# Main_v0_2.net
KiCad netlist of a schematic drawn in EAGLE
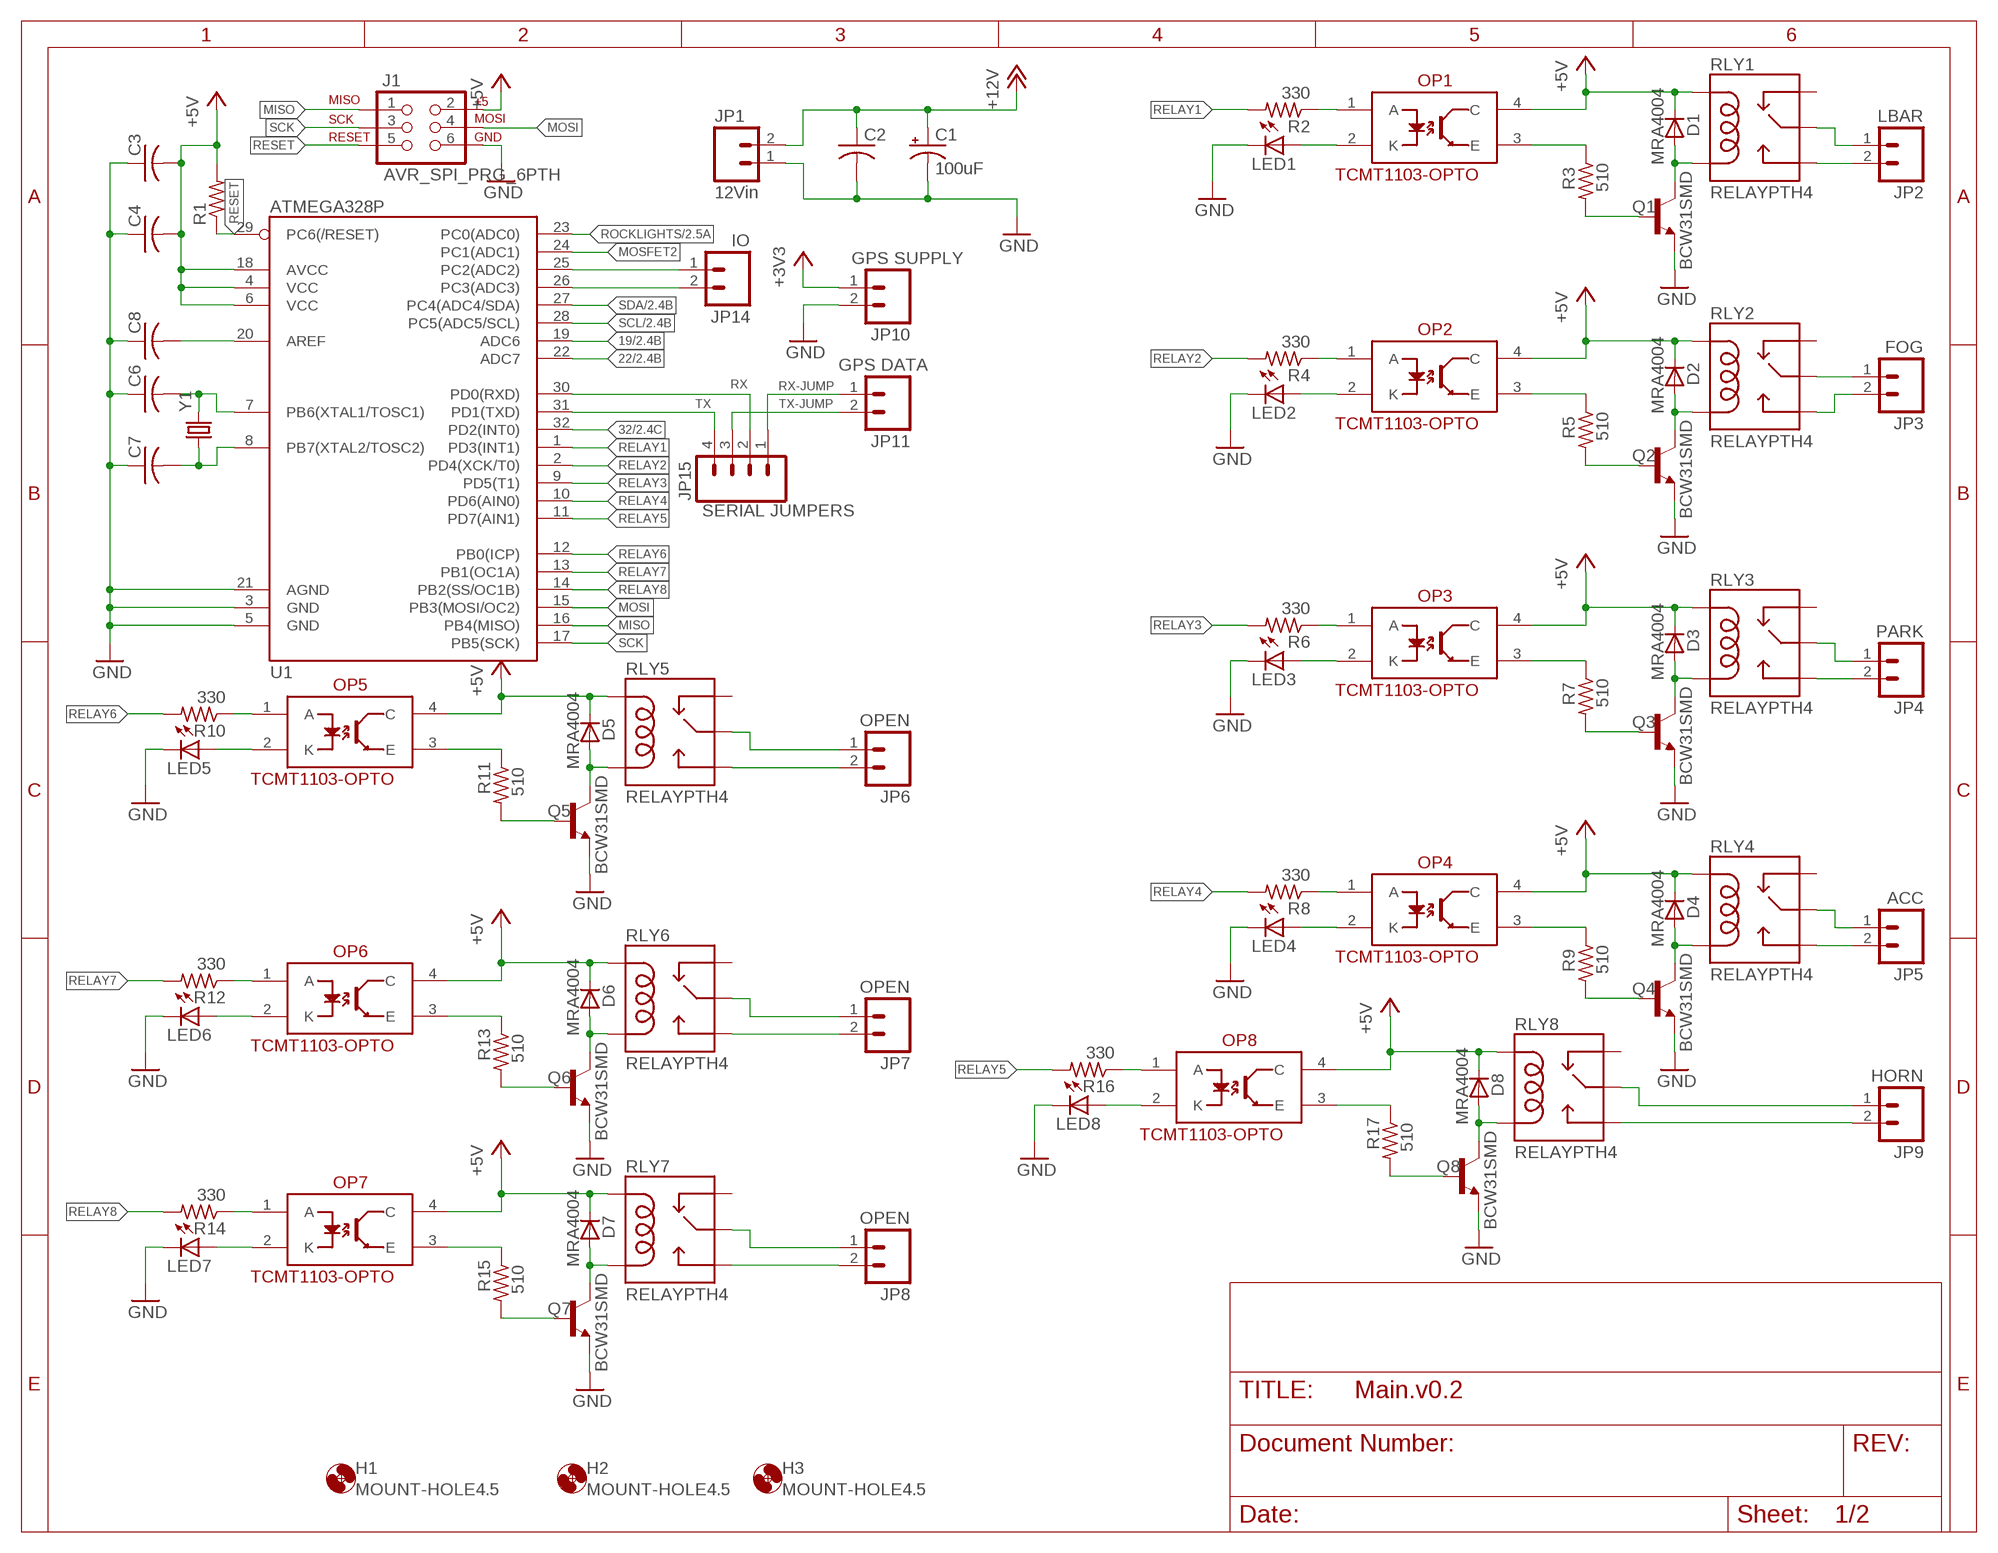
[diagram p0: schematic, sheet 1]
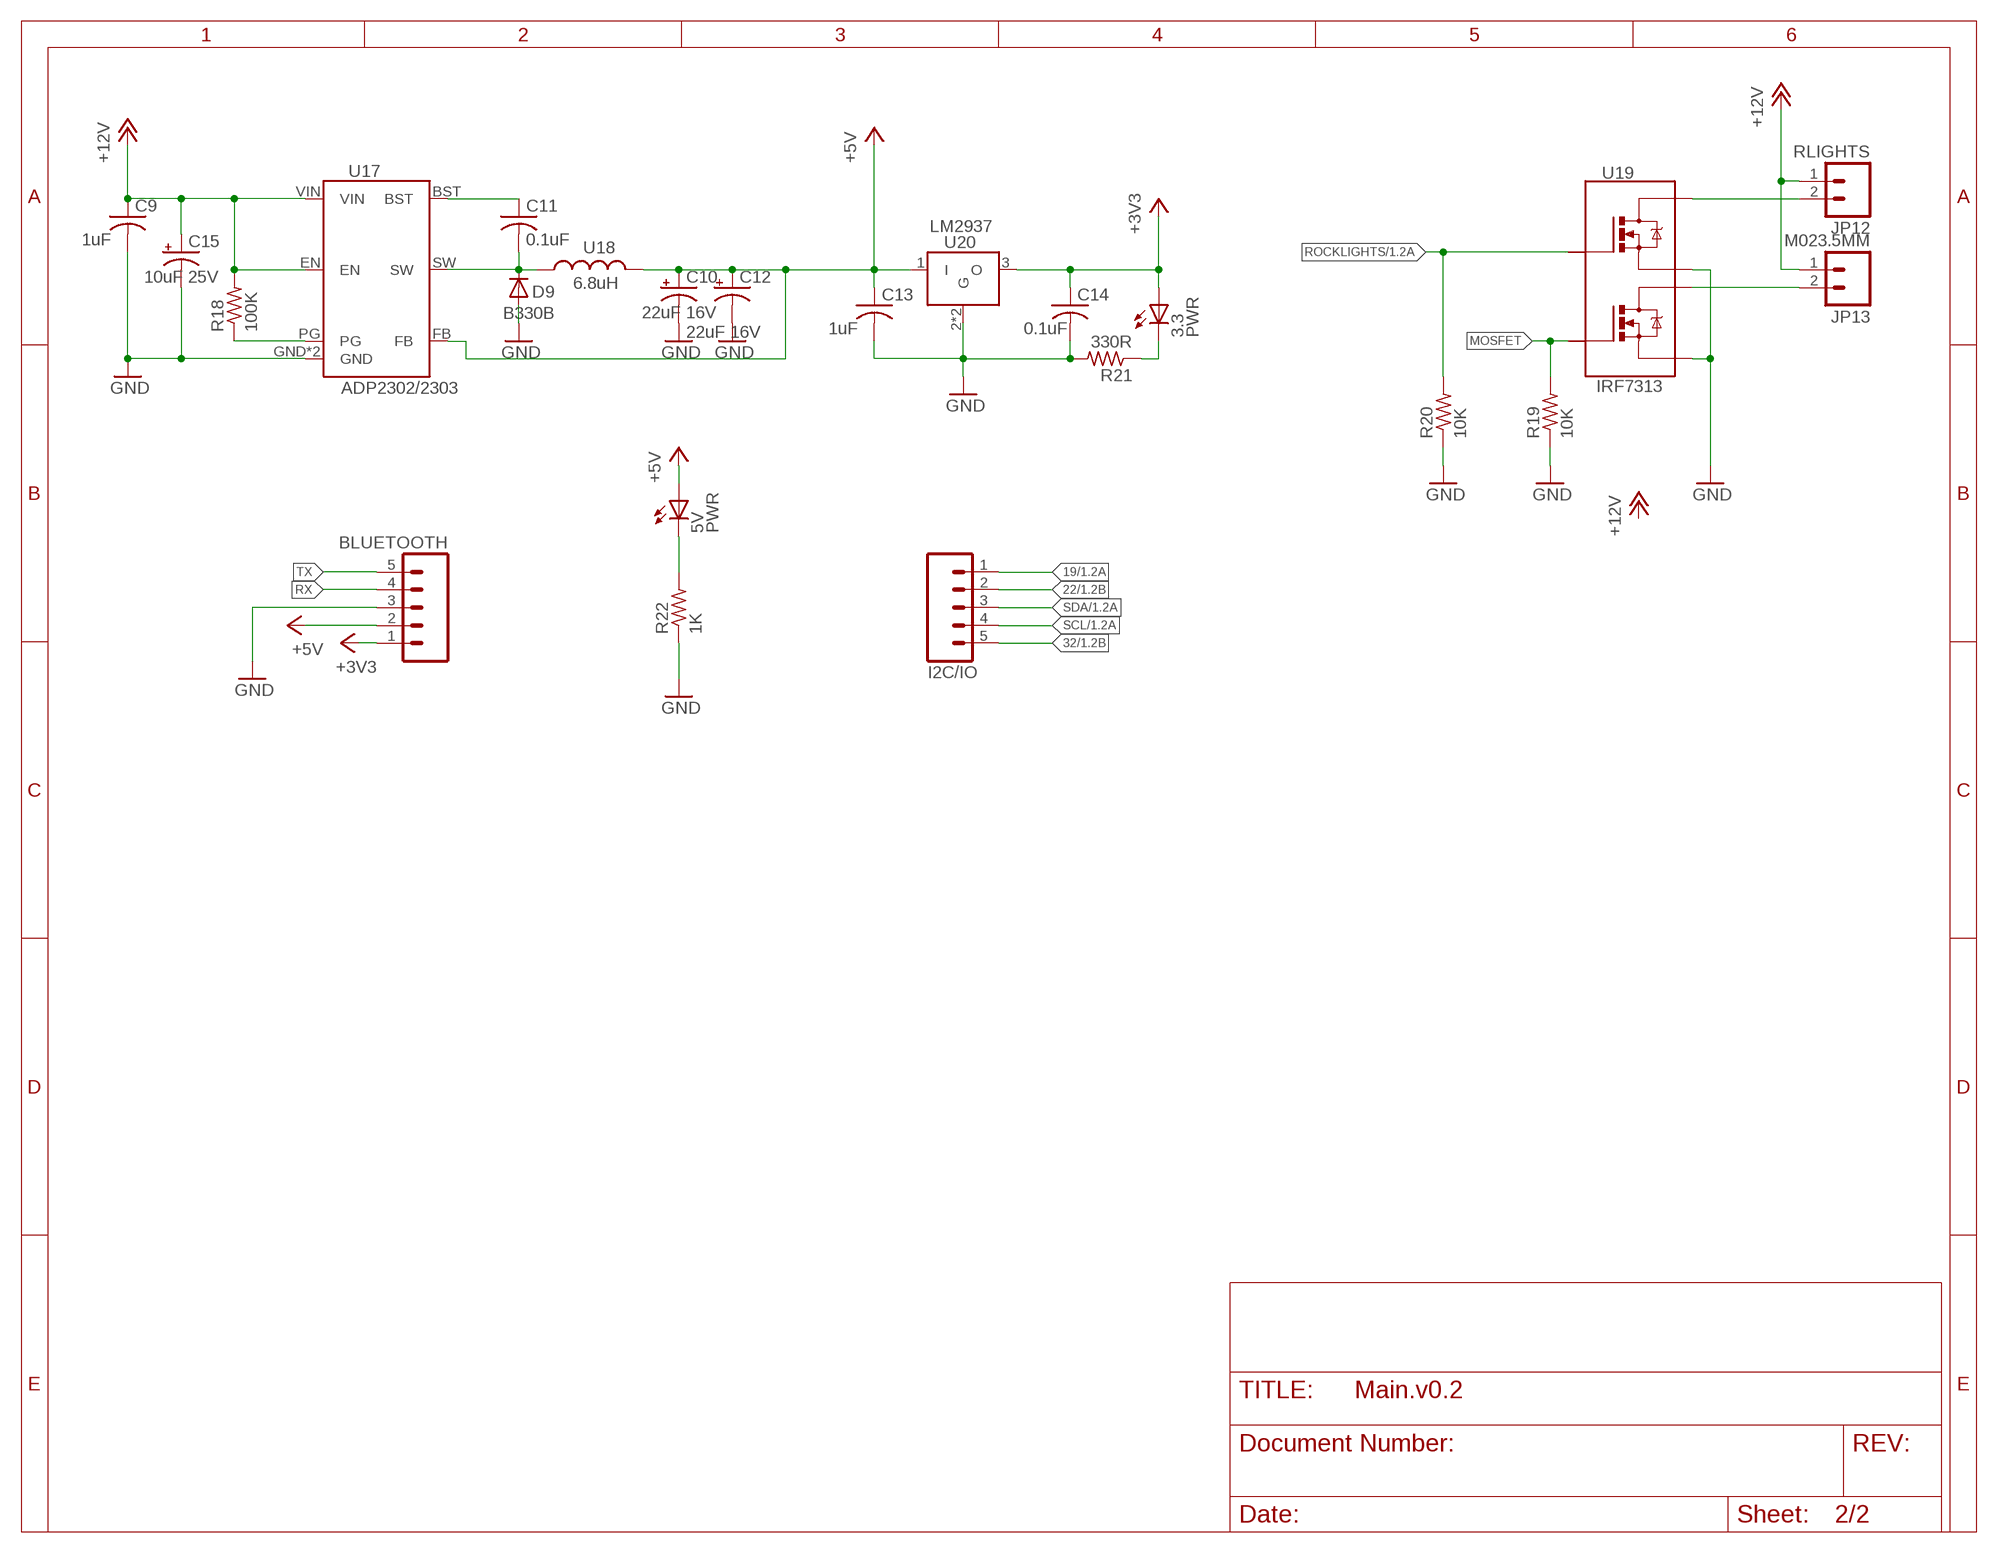
[diagram p1: schematic, sheet 2]

(export (version "E")
  (design (tool "Eeschema 10.0.6"))
  (components
    (comp (ref "3.3")
      (value "PWR")
      (footprint "eagle-import:LED-1206")
      (libsource (lib "eagle-import") (part "LED1206"))
    )
    (comp (ref "5V")
      (value "PWR")
      (footprint "eagle-import:LED-1206")
      (libsource (lib "eagle-import") (part "LED1206"))
    )
    (comp (ref "BLUETOOTH")
      (value "M05PTH")
      (footprint "eagle-import:1X05")
      (libsource (lib "eagle-import") (part "M05PTH"))
    )
    (comp (ref "C9")
      (value "1uF")
      (footprint "eagle-import:C1206")
      (libsource (lib "eagle-import") (part "C-USC1206"))
    )
    (comp (ref "C10")
      (value "22uF 16V")
      (footprint "eagle-import:PANASONIC_E")
      (libsource (lib "eagle-import") (part "CPOL-USE"))
    )
    (comp (ref "C11")
      (value "0.1uF")
      (footprint "eagle-import:C1206")
      (libsource (lib "eagle-import") (part "C-USC1206"))
    )
    (comp (ref "C12")
      (value "22uF 16V")
      (footprint "eagle-import:PANASONIC_E")
      (libsource (lib "eagle-import") (part "CPOL-USE"))
    )
    (comp (ref "C13")
      (value "1uF")
      (footprint "eagle-import:C1206")
      (libsource (lib "eagle-import") (part "C-USC1206"))
    )
    (comp (ref "C14")
      (value "0.1uF")
      (footprint "eagle-import:C1206")
      (libsource (lib "eagle-import") (part "C-USC1206"))
    )
    (comp (ref "C15")
      (value "10uF 25V")
      (footprint "eagle-import:PANASONIC_E")
      (libsource (lib "eagle-import") (part "CPOL-USE"))
    )
    (comp (ref "D9")
      (value "B330B")
      (footprint "eagle-import:DO214AA")
      (libsource (lib "eagle-import") (part "DIODE-DO214AA"))
    )
    (comp (ref "I2C/IO")
      (value "M05PTH")
      (footprint "eagle-import:1X05")
      (libsource (lib "eagle-import") (part "M05PTH"))
    )
    (comp (ref "JP12")
      (value "RLIGHTS")
      (footprint "eagle-import:SCREWTERMINAL-3.5MM-2")
      (libsource (lib "eagle-import") (part "M023.5MM"))
    )
    (comp (ref "JP13")
      (value "M023.5MM")
      (footprint "eagle-import:SCREWTERMINAL-3.5MM-2")
      (libsource (lib "eagle-import") (part "M023.5MM"))
    )
    (comp (ref "R18")
      (value "100K")
      (footprint "eagle-import:R1206")
      (libsource (lib "eagle-import") (part "R-US_R1206"))
    )
    (comp (ref "R19")
      (value "10K")
      (footprint "eagle-import:R1206")
      (libsource (lib "eagle-import") (part "R-US_R1206"))
    )
    (comp (ref "R20")
      (value "10K")
      (footprint "eagle-import:R1206")
      (libsource (lib "eagle-import") (part "R-US_R1206"))
    )
    (comp (ref "R21")
      (value "330R")
      (footprint "eagle-import:R1206")
      (libsource (lib "eagle-import") (part "R-US_R1206"))
    )
    (comp (ref "R22")
      (value "1K")
      (footprint "eagle-import:R1206")
      (libsource (lib "eagle-import") (part "R-US_R1206"))
    )
    (comp (ref "U17")
      (value "ADP2302/2303")
      (footprint "eagle-import:8SOIC")
      (libsource (lib "eagle-import") (part "ADP2302/2303"))
    )
    (comp (ref "U18")
      (value "6.8uH")
      (footprint "eagle-import:INDUCTOR")
      (libsource (lib "eagle-import") (part "INDUCTOR"))
    )
    (comp (ref "U19")
      (value "IRF7313")
      (footprint "eagle-import:SO-8")
      (libsource (lib "eagle-import") (part "IRF7313"))
    )
    (comp (ref "U20")
      (value "LM2937")
      (footprint "eagle-import:SOT223")
      (libsource (lib "eagle-import") (part "LM2937"))
    )
    (comp (ref "C1")
      (value "100uF")
      (footprint "eagle-import:PANASONIC_F")
      (libsource (lib "eagle-import") (part "CPOL-USF"))
    )
    (comp (ref "C2")
      (value "C-USC1206")
      (footprint "eagle-import:C1206")
      (libsource (lib "eagle-import") (part "C-USC1206"))
    )
    (comp (ref "C3")
      (value "C-USC1206")
      (footprint "eagle-import:C1206")
      (libsource (lib "eagle-import") (part "C-USC1206"))
    )
    (comp (ref "C4")
      (value "C-USC1206")
      (footprint "eagle-import:C1206")
      (libsource (lib "eagle-import") (part "C-USC1206"))
    )
    (comp (ref "C6")
      (value "C-USC1206")
      (footprint "eagle-import:C1206")
      (libsource (lib "eagle-import") (part "C-USC1206"))
    )
    (comp (ref "C7")
      (value "C-USC1206")
      (footprint "eagle-import:C1206")
      (libsource (lib "eagle-import") (part "C-USC1206"))
    )
    (comp (ref "C8")
      (value "C-USC1206")
      (footprint "eagle-import:C1206")
      (libsource (lib "eagle-import") (part "C-USC1206"))
    )
    (comp (ref "D1")
      (value "MRA4004")
      (footprint "eagle-import:SMA-DIODE_ALT")
      (libsource (lib "eagle-import") (part "DIODESMA-ALT"))
    )
    (comp (ref "D2")
      (value "MRA4004")
      (footprint "eagle-import:SMA-DIODE_ALT")
      (libsource (lib "eagle-import") (part "DIODESMA-ALT"))
    )
    (comp (ref "D3")
      (value "MRA4004")
      (footprint "eagle-import:SMA-DIODE_ALT")
      (libsource (lib "eagle-import") (part "DIODESMA-ALT"))
    )
    (comp (ref "D4")
      (value "MRA4004")
      (footprint "eagle-import:SMA-DIODE_ALT")
      (libsource (lib "eagle-import") (part "DIODESMA-ALT"))
    )
    (comp (ref "D5")
      (value "MRA4004")
      (footprint "eagle-import:SMA-DIODE_ALT")
      (libsource (lib "eagle-import") (part "DIODESMA-ALT"))
    )
    (comp (ref "D6")
      (value "MRA4004")
      (footprint "eagle-import:SMA-DIODE_ALT")
      (libsource (lib "eagle-import") (part "DIODESMA-ALT"))
    )
    (comp (ref "D7")
      (value "MRA4004")
      (footprint "eagle-import:SMA-DIODE_ALT")
      (libsource (lib "eagle-import") (part "DIODESMA-ALT"))
    )
    (comp (ref "D8")
      (value "MRA4004")
      (footprint "eagle-import:SMA-DIODE_ALT")
      (libsource (lib "eagle-import") (part "DIODESMA-ALT"))
    )
    (comp (ref "H1")
      (value "MOUNT-HOLE4.5")
      (footprint "eagle-import:4,5")
      (libsource (lib "eagle-import") (part "MOUNT-HOLE4.5"))
    )
    (comp (ref "H2")
      (value "MOUNT-HOLE4.5")
      (footprint "eagle-import:4,5")
      (libsource (lib "eagle-import") (part "MOUNT-HOLE4.5"))
    )
    (comp (ref "H3")
      (value "MOUNT-HOLE4.5")
      (footprint "eagle-import:4,5")
      (libsource (lib "eagle-import") (part "MOUNT-HOLE4.5"))
    )
    (comp (ref "J1")
      (value "AVR_SPI_PRG_6PTH")
      (footprint "eagle-import:2X3")
      (libsource (lib "eagle-import") (part "AVR_SPI_PRG_6PTH"))
    )
    (comp (ref "JP1")
      (value "12Vin")
      (footprint "eagle-import:SCREWTERMINAL-3.5MM-2")
      (libsource (lib "eagle-import") (part "M023.5MM"))
    )
    (comp (ref "JP2")
      (value "LBAR")
      (footprint "eagle-import:SCREWTERMINAL-3.5MM-2")
      (libsource (lib "eagle-import") (part "M023.5MM"))
    )
    (comp (ref "JP3")
      (value "FOG")
      (footprint "eagle-import:SCREWTERMINAL-3.5MM-2")
      (libsource (lib "eagle-import") (part "M023.5MM"))
    )
    (comp (ref "JP4")
      (value "PARK")
      (footprint "eagle-import:SCREWTERMINAL-3.5MM-2")
      (libsource (lib "eagle-import") (part "M023.5MM"))
    )
    (comp (ref "JP5")
      (value "ACC")
      (footprint "eagle-import:SCREWTERMINAL-3.5MM-2")
      (libsource (lib "eagle-import") (part "M023.5MM"))
    )
    (comp (ref "JP6")
      (value "OPEN")
      (footprint "eagle-import:SCREWTERMINAL-3.5MM-2")
      (libsource (lib "eagle-import") (part "M023.5MM"))
    )
    (comp (ref "JP7")
      (value "OPEN")
      (footprint "eagle-import:SCREWTERMINAL-3.5MM-2")
      (libsource (lib "eagle-import") (part "M023.5MM"))
    )
    (comp (ref "JP8")
      (value "OPEN")
      (footprint "eagle-import:SCREWTERMINAL-3.5MM-2")
      (libsource (lib "eagle-import") (part "M023.5MM"))
    )
    (comp (ref "JP9")
      (value "HORN")
      (footprint "eagle-import:SCREWTERMINAL-3.5MM-2")
      (libsource (lib "eagle-import") (part "M023.5MM"))
    )
    (comp (ref "JP10")
      (value "GPS SUPPLY")
      (footprint "eagle-import:SCREWTERMINAL-3.5MM-2")
      (libsource (lib "eagle-import") (part "M023.5MM"))
    )
    (comp (ref "JP11")
      (value "GPS DATA")
      (footprint "eagle-import:SCREWTERMINAL-3.5MM-2")
      (libsource (lib "eagle-import") (part "M023.5MM"))
    )
    (comp (ref "JP14")
      (value "IO")
      (footprint "eagle-import:SCREWTERMINAL-3.5MM-2")
      (libsource (lib "eagle-import") (part "M023.5MM"))
    )
    (comp (ref "JP15")
      (value "SERIAL JUMPERS")
      (footprint "eagle-import:1X04")
      (libsource (lib "eagle-import") (part "M04PTH"))
    )
    (comp (ref "LED1")
      (value "LED1206")
      (footprint "eagle-import:LED-1206")
      (libsource (lib "eagle-import") (part "LED1206"))
    )
    (comp (ref "LED2")
      (value "LED1206")
      (footprint "eagle-import:LED-1206")
      (libsource (lib "eagle-import") (part "LED1206"))
    )
    (comp (ref "LED3")
      (value "LED1206")
      (footprint "eagle-import:LED-1206")
      (libsource (lib "eagle-import") (part "LED1206"))
    )
    (comp (ref "LED4")
      (value "LED1206")
      (footprint "eagle-import:LED-1206")
      (libsource (lib "eagle-import") (part "LED1206"))
    )
    (comp (ref "LED5")
      (value "LED1206")
      (footprint "eagle-import:LED-1206")
      (libsource (lib "eagle-import") (part "LED1206"))
    )
    (comp (ref "LED6")
      (value "LED1206")
      (footprint "eagle-import:LED-1206")
      (libsource (lib "eagle-import") (part "LED1206"))
    )
    (comp (ref "LED7")
      (value "LED1206")
      (footprint "eagle-import:LED-1206")
      (libsource (lib "eagle-import") (part "LED1206"))
    )
    (comp (ref "LED8")
      (value "LED1206")
      (footprint "eagle-import:LED-1206")
      (libsource (lib "eagle-import") (part "LED1206"))
    )
    (comp (ref "OP1")
      (value "TCMT1103-OPTO")
      (footprint "eagle-import:SSOP-4")
      (libsource (lib "eagle-import") (part "TCMT1103-OPTO"))
    )
    (comp (ref "OP2")
      (value "TCMT1103-OPTO")
      (footprint "eagle-import:SSOP-4")
      (libsource (lib "eagle-import") (part "TCMT1103-OPTO"))
    )
    (comp (ref "OP3")
      (value "TCMT1103-OPTO")
      (footprint "eagle-import:SSOP-4")
      (libsource (lib "eagle-import") (part "TCMT1103-OPTO"))
    )
    (comp (ref "OP4")
      (value "TCMT1103-OPTO")
      (footprint "eagle-import:SSOP-4")
      (libsource (lib "eagle-import") (part "TCMT1103-OPTO"))
    )
    (comp (ref "OP5")
      (value "TCMT1103-OPTO")
      (footprint "eagle-import:SSOP-4")
      (libsource (lib "eagle-import") (part "TCMT1103-OPTO"))
    )
    (comp (ref "OP6")
      (value "TCMT1103-OPTO")
      (footprint "eagle-import:SSOP-4")
      (libsource (lib "eagle-import") (part "TCMT1103-OPTO"))
    )
    (comp (ref "OP7")
      (value "TCMT1103-OPTO")
      (footprint "eagle-import:SSOP-4")
      (libsource (lib "eagle-import") (part "TCMT1103-OPTO"))
    )
    (comp (ref "OP8")
      (value "TCMT1103-OPTO")
      (footprint "eagle-import:SSOP-4")
      (libsource (lib "eagle-import") (part "TCMT1103-OPTO"))
    )
    (comp (ref "Q1")
      (value "BCW31SMD")
      (footprint "eagle-import:SOT23-BEC")
      (libsource (lib "eagle-import") (part "BCW31SMD"))
    )
    (comp (ref "Q2")
      (value "BCW31SMD")
      (footprint "eagle-import:SOT23-BEC")
      (libsource (lib "eagle-import") (part "BCW31SMD"))
    )
    (comp (ref "Q3")
      (value "BCW31SMD")
      (footprint "eagle-import:SOT23-BEC")
      (libsource (lib "eagle-import") (part "BCW31SMD"))
    )
    (comp (ref "Q4")
      (value "BCW31SMD")
      (footprint "eagle-import:SOT23-BEC")
      (libsource (lib "eagle-import") (part "BCW31SMD"))
    )
    (comp (ref "Q5")
      (value "BCW31SMD")
      (footprint "eagle-import:SOT23-BEC")
      (libsource (lib "eagle-import") (part "BCW31SMD"))
    )
    (comp (ref "Q6")
      (value "BCW31SMD")
      (footprint "eagle-import:SOT23-BEC")
      (libsource (lib "eagle-import") (part "BCW31SMD"))
    )
    (comp (ref "Q7")
      (value "BCW31SMD")
      (footprint "eagle-import:SOT23-BEC")
      (libsource (lib "eagle-import") (part "BCW31SMD"))
    )
    (comp (ref "Q8")
      (value "BCW31SMD")
      (footprint "eagle-import:SOT23-BEC")
      (libsource (lib "eagle-import") (part "BCW31SMD"))
    )
    (comp (ref "R1")
      (value "R-US_R1206")
      (footprint "eagle-import:R1206")
      (libsource (lib "eagle-import") (part "R-US_R1206"))
    )
    (comp (ref "R2")
      (value "330")
      (footprint "eagle-import:R1206")
      (libsource (lib "eagle-import") (part "R-US_R1206"))
    )
    (comp (ref "R3")
      (value "510")
      (footprint "eagle-import:R1206")
      (libsource (lib "eagle-import") (part "R-US_R1206"))
    )
    (comp (ref "R4")
      (value "330")
      (footprint "eagle-import:R1206")
      (libsource (lib "eagle-import") (part "R-US_R1206"))
    )
    (comp (ref "R5")
      (value "510")
      (footprint "eagle-import:R1206")
      (libsource (lib "eagle-import") (part "R-US_R1206"))
    )
    (comp (ref "R6")
      (value "330")
      (footprint "eagle-import:R1206")
      (libsource (lib "eagle-import") (part "R-US_R1206"))
    )
    (comp (ref "R7")
      (value "510")
      (footprint "eagle-import:R1206")
      (libsource (lib "eagle-import") (part "R-US_R1206"))
    )
    (comp (ref "R8")
      (value "330")
      (footprint "eagle-import:R1206")
      (libsource (lib "eagle-import") (part "R-US_R1206"))
    )
    (comp (ref "R9")
      (value "510")
      (footprint "eagle-import:R1206")
      (libsource (lib "eagle-import") (part "R-US_R1206"))
    )
    (comp (ref "R10")
      (value "330")
      (footprint "eagle-import:R1206")
      (libsource (lib "eagle-import") (part "R-US_R1206"))
    )
    (comp (ref "R11")
      (value "510")
      (footprint "eagle-import:R1206")
      (libsource (lib "eagle-import") (part "R-US_R1206"))
    )
    (comp (ref "R12")
      (value "330")
      (footprint "eagle-import:R1206")
      (libsource (lib "eagle-import") (part "R-US_R1206"))
    )
    (comp (ref "R13")
      (value "510")
      (footprint "eagle-import:R1206")
      (libsource (lib "eagle-import") (part "R-US_R1206"))
    )
    (comp (ref "R14")
      (value "330")
      (footprint "eagle-import:R1206")
      (libsource (lib "eagle-import") (part "R-US_R1206"))
    )
    (comp (ref "R15")
      (value "510")
      (footprint "eagle-import:R1206")
      (libsource (lib "eagle-import") (part "R-US_R1206"))
    )
    (comp (ref "R16")
      (value "330")
      (footprint "eagle-import:R1206")
      (libsource (lib "eagle-import") (part "R-US_R1206"))
    )
    (comp (ref "R17")
      (value "510")
      (footprint "eagle-import:R1206")
      (libsource (lib "eagle-import") (part "R-US_R1206"))
    )
    (comp (ref "RLY1")
      (value "RELAYPTH4")
      (footprint "eagle-import:RELAY-JZC")
      (libsource (lib "eagle-import") (part "RELAYPTH4"))
    )
    (comp (ref "RLY2")
      (value "RELAYPTH4")
      (footprint "eagle-import:RELAY-JZC")
      (libsource (lib "eagle-import") (part "RELAYPTH4"))
    )
    (comp (ref "RLY3")
      (value "RELAYPTH4")
      (footprint "eagle-import:RELAY-JZC")
      (libsource (lib "eagle-import") (part "RELAYPTH4"))
    )
    (comp (ref "RLY4")
      (value "RELAYPTH4")
      (footprint "eagle-import:RELAY-JZC")
      (libsource (lib "eagle-import") (part "RELAYPTH4"))
    )
    (comp (ref "RLY5")
      (value "RELAYPTH4")
      (footprint "eagle-import:RELAY-JZC")
      (libsource (lib "eagle-import") (part "RELAYPTH4"))
    )
    (comp (ref "RLY6")
      (value "RELAYPTH4")
      (footprint "eagle-import:RELAY-JZC")
      (libsource (lib "eagle-import") (part "RELAYPTH4"))
    )
    (comp (ref "RLY7")
      (value "RELAYPTH4")
      (footprint "eagle-import:RELAY-JZC")
      (libsource (lib "eagle-import") (part "RELAYPTH4"))
    )
    (comp (ref "RLY8")
      (value "RELAYPTH4")
      (footprint "eagle-import:RELAY-JZC")
      (libsource (lib "eagle-import") (part "RELAYPTH4"))
    )
    (comp (ref "U1")
      (value "ATMEGA328P")
      (footprint "eagle-import:TQFP32-08")
      (libsource (lib "eagle-import") (part "ATMEGA328_SMT"))
    )
    (comp (ref "Y1")
      (value "CRYSTALSMD")
      (footprint "eagle-import:HC49UP")
      (libsource (lib "eagle-import") (part "CRYSTALSMD"))
    )
  )
  (nets
    (net (code "1") (name "+3V3") (class "Default")
      (node (ref "3.3") (pin "A") (pinfunction "A_A") (pintype "passive"))
      (node (ref "BLUETOOTH") (pin "1") (pinfunction "1_1") (pintype "passive"))
      (node (ref "C14") (pin "1") (pinfunction "1_1") (pintype "passive"))
      (node (ref "JP10") (pin "1") (pinfunction "1_1") (pintype "passive"))
      (node (ref "U20") (pin "3") (pinfunction "O_3") (pintype "bidirectional"))
    )
    (net (code "2") (name "+5V") (class "Default")
      (node (ref "5V") (pin "A") (pinfunction "A_A") (pintype "passive"))
      (node (ref "BLUETOOTH") (pin "2") (pinfunction "2_2") (pintype "passive"))
      (node (ref "C10") (pin "+") (pinfunction "+_+") (pintype "passive"))
      (node (ref "C12") (pin "+") (pinfunction "+_+") (pintype "passive"))
      (node (ref "C13") (pin "1") (pinfunction "1_1") (pintype "passive"))
      (node (ref "C3") (pin "2") (pinfunction "2_2") (pintype "passive"))
      (node (ref "C4") (pin "2") (pinfunction "2_2") (pintype "passive"))
      (node (ref "D1") (pin "C") (pinfunction "C_C") (pintype "passive"))
      (node (ref "D2") (pin "C") (pinfunction "C_C") (pintype "passive"))
      (node (ref "D3") (pin "C") (pinfunction "C_C") (pintype "passive"))
      (node (ref "D4") (pin "C") (pinfunction "C_C") (pintype "passive"))
      (node (ref "D5") (pin "C") (pinfunction "C_C") (pintype "passive"))
      (node (ref "D6") (pin "C") (pinfunction "C_C") (pintype "passive"))
      (node (ref "D7") (pin "C") (pinfunction "C_C") (pintype "passive"))
      (node (ref "D8") (pin "C") (pinfunction "C_C") (pintype "passive"))
      (node (ref "J1") (pin "2") (pinfunction "2_2") (pintype "passive"))
      (node (ref "OP1") (pin "4") (pinfunction "C_4") (pintype "bidirectional"))
      (node (ref "OP2") (pin "4") (pinfunction "C_4") (pintype "bidirectional"))
      (node (ref "OP3") (pin "4") (pinfunction "C_4") (pintype "bidirectional"))
      (node (ref "OP4") (pin "4") (pinfunction "C_4") (pintype "bidirectional"))
      (node (ref "OP5") (pin "4") (pinfunction "C_4") (pintype "bidirectional"))
      (node (ref "OP6") (pin "4") (pinfunction "C_4") (pintype "bidirectional"))
      (node (ref "OP7") (pin "4") (pinfunction "C_4") (pintype "bidirectional"))
      (node (ref "OP8") (pin "4") (pinfunction "C_4") (pintype "bidirectional"))
      (node (ref "R1") (pin "2") (pinfunction "2_2") (pintype "passive"))
      (node (ref "RLY1") (pin "5") (pinfunction "COIL1_5") (pintype "bidirectional"))
      (node (ref "RLY2") (pin "5") (pinfunction "COIL1_5") (pintype "bidirectional"))
      (node (ref "RLY3") (pin "5") (pinfunction "COIL1_5") (pintype "bidirectional"))
      (node (ref "RLY4") (pin "5") (pinfunction "COIL1_5") (pintype "bidirectional"))
      (node (ref "RLY5") (pin "5") (pinfunction "COIL1_5") (pintype "bidirectional"))
      (node (ref "RLY6") (pin "5") (pinfunction "COIL1_5") (pintype "bidirectional"))
      (node (ref "RLY7") (pin "5") (pinfunction "COIL1_5") (pintype "bidirectional"))
      (node (ref "RLY8") (pin "5") (pinfunction "COIL1_5") (pintype "bidirectional"))
      (node (ref "U1") (pin "18") (pinfunction "AVCC_18") (pintype "bidirectional"))
      (node (ref "U1") (pin "4") (pinfunction "VCC_4") (pintype "bidirectional"))
      (node (ref "U1") (pin "6") (pinfunction "VCC_6") (pintype "bidirectional"))
      (node (ref "U17") (pin "FB") (pinfunction "FB_FB") (pintype "bidirectional"))
      (node (ref "U18") (pin "P$2") (pinfunction "2_P$2") (pintype "passive"))
      (node (ref "U20") (pin "1") (pinfunction "I_1") (pintype "bidirectional"))
    )
    (net (code "3") (name "+12V") (class "Default")
      (node (ref "C1") (pin "+") (pinfunction "+_+") (pintype "passive"))
      (node (ref "C15") (pin "+") (pinfunction "+_+") (pintype "passive"))
      (node (ref "C2") (pin "1") (pinfunction "1_1") (pintype "passive"))
      (node (ref "C9") (pin "1") (pinfunction "1_1") (pintype "passive"))
      (node (ref "JP1") (pin "2") (pinfunction "2_2") (pintype "passive"))
      (node (ref "JP12") (pin "1") (pinfunction "1_1") (pintype "passive"))
      (node (ref "JP13") (pin "1") (pinfunction "1_1") (pintype "passive"))
      (node (ref "R18") (pin "2") (pinfunction "2_2") (pintype "passive"))
      (node (ref "U17") (pin "EN") (pinfunction "EN_EN") (pintype "bidirectional"))
      (node (ref "U17") (pin "VIN") (pinfunction "VIN_VIN") (pintype "bidirectional"))
    )
    (net (code "4") (name "19") (class "Default")
      (node (ref "I2C/IO") (pin "1") (pinfunction "1_1") (pintype "passive"))
      (node (ref "U1") (pin "19") (pinfunction "ADC6_19") (pintype "bidirectional"))
    )
    (net (code "5") (name "22") (class "Default")
      (node (ref "I2C/IO") (pin "2") (pinfunction "2_2") (pintype "passive"))
      (node (ref "U1") (pin "22") (pinfunction "ADC7_22") (pintype "bidirectional"))
    )
    (net (code "6") (name "32") (class "Default")
      (node (ref "I2C/IO") (pin "5") (pinfunction "5_5") (pintype "passive"))
      (node (ref "U1") (pin "32") (pinfunction "PD2(INT0)_32") (pintype "bidirectional"))
    )
    (net (code "7") (name "GND") (class "Default")
      (node (ref "BLUETOOTH") (pin "3") (pinfunction "3_3") (pintype "passive"))
      (node (ref "C1") (pin "-") (pinfunction "-_-") (pintype "passive"))
      (node (ref "C10") (pin "-") (pinfunction "-_-") (pintype "passive"))
      (node (ref "C12") (pin "-") (pinfunction "-_-") (pintype "passive"))
      (node (ref "C13") (pin "2") (pinfunction "2_2") (pintype "passive"))
      (node (ref "C14") (pin "2") (pinfunction "2_2") (pintype "passive"))
      (node (ref "C15") (pin "-") (pinfunction "-_-") (pintype "passive"))
      (node (ref "C2") (pin "2") (pinfunction "2_2") (pintype "passive"))
      (node (ref "C3") (pin "1") (pinfunction "1_1") (pintype "passive"))
      (node (ref "C4") (pin "1") (pinfunction "1_1") (pintype "passive"))
      (node (ref "C6") (pin "1") (pinfunction "1_1") (pintype "passive"))
      (node (ref "C7") (pin "1") (pinfunction "1_1") (pintype "passive"))
      (node (ref "C8") (pin "1") (pinfunction "1_1") (pintype "passive"))
      (node (ref "C9") (pin "2") (pinfunction "2_2") (pintype "passive"))
      (node (ref "D9") (pin "A") (pinfunction "A_A") (pintype "passive"))
      (node (ref "J1") (pin "6") (pinfunction "6_6") (pintype "passive"))
      (node (ref "JP1") (pin "1") (pinfunction "1_1") (pintype "passive"))
      (node (ref "JP10") (pin "2") (pinfunction "2_2") (pintype "passive"))
      (node (ref "LED1") (pin "C") (pinfunction "C_C") (pintype "passive"))
      (node (ref "LED2") (pin "C") (pinfunction "C_C") (pintype "passive"))
      (node (ref "LED3") (pin "C") (pinfunction "C_C") (pintype "passive"))
      (node (ref "LED4") (pin "C") (pinfunction "C_C") (pintype "passive"))
      (node (ref "LED5") (pin "C") (pinfunction "C_C") (pintype "passive"))
      (node (ref "LED6") (pin "C") (pinfunction "C_C") (pintype "passive"))
      (node (ref "LED7") (pin "C") (pinfunction "C_C") (pintype "passive"))
      (node (ref "LED8") (pin "C") (pinfunction "C_C") (pintype "passive"))
      (node (ref "Q1") (pin "E") (pinfunction "E_E") (pintype "passive"))
      (node (ref "Q2") (pin "E") (pinfunction "E_E") (pintype "passive"))
      (node (ref "Q3") (pin "E") (pinfunction "E_E") (pintype "passive"))
      (node (ref "Q4") (pin "E") (pinfunction "E_E") (pintype "passive"))
      (node (ref "Q5") (pin "E") (pinfunction "E_E") (pintype "passive"))
      (node (ref "Q6") (pin "E") (pinfunction "E_E") (pintype "passive"))
      (node (ref "Q7") (pin "E") (pinfunction "E_E") (pintype "passive"))
      (node (ref "Q8") (pin "E") (pinfunction "E_E") (pintype "passive"))
      (node (ref "R19") (pin "1") (pinfunction "1_1") (pintype "passive"))
      (node (ref "R20") (pin "1") (pinfunction "1_1") (pintype "passive"))
      (node (ref "R21") (pin "2") (pinfunction "2_2") (pintype "passive"))
      (node (ref "R22") (pin "1") (pinfunction "1_1") (pintype "passive"))
      (node (ref "U1") (pin "21") (pinfunction "AGND_21") (pintype "bidirectional"))
      (node (ref "U1") (pin "3") (pinfunction "GND_3") (pintype "bidirectional"))
      (node (ref "U1") (pin "5") (pinfunction "GND_5") (pintype "bidirectional"))
      (node (ref "U17") (pin "GND") (pinfunction "GND_GND") (pintype "bidirectional"))
      (node (ref "U17") (pin "NC") (pinfunction "GND_NC") (pintype "bidirectional"))
      (node (ref "U19") (pin "1") (pinfunction "S_1") (pintype "passive"))
      (node (ref "U19") (pin "3") (pinfunction "S1_3") (pintype "passive"))
      (node (ref "U20") (pin "2") (pinfunction "G_2") (pintype "bidirectional"))
      (node (ref "U20") (pin "4") (pinfunction "G_4") (pintype "bidirectional"))
    )
    (net (code "8") (name "MISO") (class "Default")
      (node (ref "J1") (pin "1") (pinfunction "1_1") (pintype "passive"))
      (node (ref "U1") (pin "16") (pinfunction "PB4(MISO)_16") (pintype "bidirectional"))
    )
    (net (code "9") (name "MOSFET") (class "Default")
      (node (ref "R19") (pin "2") (pinfunction "2_2") (pintype "passive"))
      (node (ref "U19") (pin "4") (pinfunction "G1_4") (pintype "passive"))
    )
    (net (code "10") (name "MOSFET2") (class "Default")
      (node (ref "U1") (pin "24") (pinfunction "PC1(ADC1)_24") (pintype "bidirectional"))
    )
    (net (code "11") (name "MOSI") (class "Default")
      (node (ref "J1") (pin "4") (pinfunction "4_4") (pintype "passive"))
      (node (ref "U1") (pin "15") (pinfunction "PB3(MOSI/OC2)_15") (pintype "bidirectional"))
    )
    (net (code "12") (name "Net-(3.3-PadC)") (class "Default")
      (node (ref "3.3") (pin "C") (pinfunction "C_C") (pintype "passive"))
      (node (ref "R21") (pin "1") (pinfunction "1_1") (pintype "passive"))
    )
    (net (code "13") (name "Net-(5V-PadC)") (class "Default")
      (node (ref "5V") (pin "C") (pinfunction "C_C") (pintype "passive"))
      (node (ref "R22") (pin "2") (pinfunction "2_2") (pintype "passive"))
    )
    (net (code "14") (name "Net-(C11-Pad1)") (class "Default")
      (node (ref "C11") (pin "1") (pinfunction "1_1") (pintype "passive"))
      (node (ref "U17") (pin "BST") (pinfunction "BST_BST") (pintype "bidirectional"))
    )
    (net (code "15") (name "Net-(JP12-Pad2)") (class "Default")
      (node (ref "JP12") (pin "2") (pinfunction "2_2") (pintype "passive"))
      (node (ref "U19") (pin "7") (pinfunction "D_7") (pintype "passive"))
      (node (ref "U19") (pin "8") (pinfunction "D_8") (pintype "passive"))
    )
    (net (code "16") (name "Net-(JP13-Pad2)") (class "Default")
      (node (ref "JP13") (pin "2") (pinfunction "2_2") (pintype "passive"))
      (node (ref "U19") (pin "5") (pinfunction "D1_5") (pintype "passive"))
      (node (ref "U19") (pin "6") (pinfunction "D1_6") (pintype "passive"))
    )
    (net (code "17") (name "Net-(OP1-A)") (class "Default")
      (node (ref "OP1") (pin "1") (pinfunction "A_1") (pintype "bidirectional"))
      (node (ref "R2") (pin "1") (pinfunction "1_1") (pintype "passive"))
    )
    (net (code "18") (name "Net-(OP1-E)") (class "Default")
      (node (ref "OP1") (pin "3") (pinfunction "E_3") (pintype "bidirectional"))
      (node (ref "R3") (pin "1") (pinfunction "1_1") (pintype "passive"))
    )
    (net (code "19") (name "Net-(OP1-K)") (class "Default")
      (node (ref "LED1") (pin "A") (pinfunction "A_A") (pintype "passive"))
      (node (ref "OP1") (pin "2") (pinfunction "K_2") (pintype "bidirectional"))
    )
    (net (code "20") (name "Net-(OP2-A)") (class "Default")
      (node (ref "OP2") (pin "1") (pinfunction "A_1") (pintype "bidirectional"))
      (node (ref "R4") (pin "1") (pinfunction "1_1") (pintype "passive"))
    )
    (net (code "21") (name "Net-(OP2-E)") (class "Default")
      (node (ref "OP2") (pin "3") (pinfunction "E_3") (pintype "bidirectional"))
      (node (ref "R5") (pin "1") (pinfunction "1_1") (pintype "passive"))
    )
    (net (code "22") (name "Net-(OP2-K)") (class "Default")
      (node (ref "LED2") (pin "A") (pinfunction "A_A") (pintype "passive"))
      (node (ref "OP2") (pin "2") (pinfunction "K_2") (pintype "bidirectional"))
    )
    (net (code "23") (name "Net-(OP3-A)") (class "Default")
      (node (ref "OP3") (pin "1") (pinfunction "A_1") (pintype "bidirectional"))
      (node (ref "R6") (pin "1") (pinfunction "1_1") (pintype "passive"))
    )
    (net (code "24") (name "Net-(OP3-E)") (class "Default")
      (node (ref "OP3") (pin "3") (pinfunction "E_3") (pintype "bidirectional"))
      (node (ref "R7") (pin "1") (pinfunction "1_1") (pintype "passive"))
    )
    (net (code "25") (name "Net-(OP3-K)") (class "Default")
      (node (ref "LED3") (pin "A") (pinfunction "A_A") (pintype "passive"))
      (node (ref "OP3") (pin "2") (pinfunction "K_2") (pintype "bidirectional"))
    )
    (net (code "26") (name "Net-(OP4-A)") (class "Default")
      (node (ref "OP4") (pin "1") (pinfunction "A_1") (pintype "bidirectional"))
      (node (ref "R8") (pin "1") (pinfunction "1_1") (pintype "passive"))
    )
    (net (code "27") (name "Net-(OP4-E)") (class "Default")
      (node (ref "OP4") (pin "3") (pinfunction "E_3") (pintype "bidirectional"))
      (node (ref "R9") (pin "1") (pinfunction "1_1") (pintype "passive"))
    )
    (net (code "28") (name "Net-(OP4-K)") (class "Default")
      (node (ref "LED4") (pin "A") (pinfunction "A_A") (pintype "passive"))
      (node (ref "OP4") (pin "2") (pinfunction "K_2") (pintype "bidirectional"))
    )
    (net (code "29") (name "Net-(OP5-A)") (class "Default")
      (node (ref "OP5") (pin "1") (pinfunction "A_1") (pintype "bidirectional"))
      (node (ref "R10") (pin "1") (pinfunction "1_1") (pintype "passive"))
    )
    (net (code "30") (name "Net-(OP5-E)") (class "Default")
      (node (ref "OP5") (pin "3") (pinfunction "E_3") (pintype "bidirectional"))
      (node (ref "R11") (pin "1") (pinfunction "1_1") (pintype "passive"))
    )
    (net (code "31") (name "Net-(OP5-K)") (class "Default")
      (node (ref "LED5") (pin "A") (pinfunction "A_A") (pintype "passive"))
      (node (ref "OP5") (pin "2") (pinfunction "K_2") (pintype "bidirectional"))
    )
    (net (code "32") (name "Net-(OP6-A)") (class "Default")
      (node (ref "OP6") (pin "1") (pinfunction "A_1") (pintype "bidirectional"))
      (node (ref "R12") (pin "1") (pinfunction "1_1") (pintype "passive"))
    )
    (net (code "33") (name "Net-(OP6-E)") (class "Default")
      (node (ref "OP6") (pin "3") (pinfunction "E_3") (pintype "bidirectional"))
      (node (ref "R13") (pin "1") (pinfunction "1_1") (pintype "passive"))
    )
    (net (code "34") (name "Net-(OP6-K)") (class "Default")
      (node (ref "LED6") (pin "A") (pinfunction "A_A") (pintype "passive"))
      (node (ref "OP6") (pin "2") (pinfunction "K_2") (pintype "bidirectional"))
    )
    (net (code "35") (name "Net-(OP7-A)") (class "Default")
      (node (ref "OP7") (pin "1") (pinfunction "A_1") (pintype "bidirectional"))
      (node (ref "R14") (pin "1") (pinfunction "1_1") (pintype "passive"))
    )
    (net (code "36") (name "Net-(OP7-E)") (class "Default")
      (node (ref "OP7") (pin "3") (pinfunction "E_3") (pintype "bidirectional"))
      (node (ref "R15") (pin "1") (pinfunction "1_1") (pintype "passive"))
    )
    (net (code "37") (name "Net-(OP7-K)") (class "Default")
      (node (ref "LED7") (pin "A") (pinfunction "A_A") (pintype "passive"))
      (node (ref "OP7") (pin "2") (pinfunction "K_2") (pintype "bidirectional"))
    )
    (net (code "38") (name "Net-(OP8-A)") (class "Default")
      (node (ref "OP8") (pin "1") (pinfunction "A_1") (pintype "bidirectional"))
      (node (ref "R16") (pin "1") (pinfunction "1_1") (pintype "passive"))
    )
    (net (code "39") (name "Net-(OP8-E)") (class "Default")
      (node (ref "OP8") (pin "3") (pinfunction "E_3") (pintype "bidirectional"))
      (node (ref "R17") (pin "1") (pinfunction "1_1") (pintype "passive"))
    )
    (net (code "40") (name "Net-(OP8-K)") (class "Default")
      (node (ref "LED8") (pin "A") (pinfunction "A_A") (pintype "passive"))
      (node (ref "OP8") (pin "2") (pinfunction "K_2") (pintype "bidirectional"))
    )
    (net (code "41") (name "Net-(Q1-PadB)") (class "Default")
      (node (ref "Q1") (pin "B") (pinfunction "B_B") (pintype "passive"))
      (node (ref "R3") (pin "2") (pinfunction "2_2") (pintype "passive"))
    )
    (net (code "42") (name "Net-(Q2-PadB)") (class "Default")
      (node (ref "Q2") (pin "B") (pinfunction "B_B") (pintype "passive"))
      (node (ref "R5") (pin "2") (pinfunction "2_2") (pintype "passive"))
    )
    (net (code "43") (name "Net-(Q3-PadB)") (class "Default")
      (node (ref "Q3") (pin "B") (pinfunction "B_B") (pintype "passive"))
      (node (ref "R7") (pin "2") (pinfunction "2_2") (pintype "passive"))
    )
    (net (code "44") (name "Net-(Q4-PadB)") (class "Default")
      (node (ref "Q4") (pin "B") (pinfunction "B_B") (pintype "passive"))
      (node (ref "R9") (pin "2") (pinfunction "2_2") (pintype "passive"))
    )
    (net (code "45") (name "Net-(Q5-PadB)") (class "Default")
      (node (ref "Q5") (pin "B") (pinfunction "B_B") (pintype "passive"))
      (node (ref "R11") (pin "2") (pinfunction "2_2") (pintype "passive"))
    )
    (net (code "46") (name "Net-(Q6-PadB)") (class "Default")
      (node (ref "Q6") (pin "B") (pinfunction "B_B") (pintype "passive"))
      (node (ref "R13") (pin "2") (pinfunction "2_2") (pintype "passive"))
    )
    (net (code "47") (name "Net-(Q7-PadB)") (class "Default")
      (node (ref "Q7") (pin "B") (pinfunction "B_B") (pintype "passive"))
      (node (ref "R15") (pin "2") (pinfunction "2_2") (pintype "passive"))
    )
    (net (code "48") (name "Net-(Q8-PadB)") (class "Default")
      (node (ref "Q8") (pin "B") (pinfunction "B_B") (pintype "passive"))
      (node (ref "R17") (pin "2") (pinfunction "2_2") (pintype "passive"))
    )
    (net (code "49") (name "Net-(R18-Pad1)") (class "Default")
      (node (ref "R18") (pin "1") (pinfunction "1_1") (pintype "passive"))
      (node (ref "U17") (pin "PG") (pinfunction "PG_PG") (pintype "bidirectional"))
    )
    (net (code "50") (name "Net-(RLY1-COIL2)") (class "Default")
      (node (ref "D1") (pin "A") (pinfunction "A_A") (pintype "passive"))
      (node (ref "Q1") (pin "C") (pinfunction "C_C") (pintype "passive"))
      (node (ref "RLY1") (pin "1") (pinfunction "COIL2_1") (pintype "bidirectional"))
    )
    (net (code "51") (name "Net-(RLY1-MAIN)") (class "Default")
      (node (ref "JP2") (pin "1") (pinfunction "1_1") (pintype "passive"))
      (node (ref "RLY1") (pin "4") (pinfunction "MAIN_4") (pintype "bidirectional"))
    )
    (net (code "52") (name "Net-(RLY1-NO)") (class "Default")
      (node (ref "JP2") (pin "2") (pinfunction "2_2") (pintype "passive"))
      (node (ref "RLY1") (pin "3") (pinfunction "NO_3") (pintype "bidirectional"))
    )
    (net (code "53") (name "Net-(RLY2-COIL2)") (class "Default")
      (node (ref "D2") (pin "A") (pinfunction "A_A") (pintype "passive"))
      (node (ref "Q2") (pin "C") (pinfunction "C_C") (pintype "passive"))
      (node (ref "RLY2") (pin "1") (pinfunction "COIL2_1") (pintype "bidirectional"))
    )
    (net (code "54") (name "Net-(RLY2-MAIN)") (class "Default")
      (node (ref "JP3") (pin "1") (pinfunction "1_1") (pintype "passive"))
      (node (ref "RLY2") (pin "4") (pinfunction "MAIN_4") (pintype "bidirectional"))
    )
    (net (code "55") (name "Net-(RLY2-NO)") (class "Default")
      (node (ref "JP3") (pin "2") (pinfunction "2_2") (pintype "passive"))
      (node (ref "RLY2") (pin "3") (pinfunction "NO_3") (pintype "bidirectional"))
    )
    (net (code "56") (name "Net-(RLY3-COIL2)") (class "Default")
      (node (ref "D3") (pin "A") (pinfunction "A_A") (pintype "passive"))
      (node (ref "Q3") (pin "C") (pinfunction "C_C") (pintype "passive"))
      (node (ref "RLY3") (pin "1") (pinfunction "COIL2_1") (pintype "bidirectional"))
    )
    (net (code "57") (name "Net-(RLY3-MAIN)") (class "Default")
      (node (ref "JP4") (pin "1") (pinfunction "1_1") (pintype "passive"))
      (node (ref "RLY3") (pin "4") (pinfunction "MAIN_4") (pintype "bidirectional"))
    )
    (net (code "58") (name "Net-(RLY3-NO)") (class "Default")
      (node (ref "JP4") (pin "2") (pinfunction "2_2") (pintype "passive"))
      (node (ref "RLY3") (pin "3") (pinfunction "NO_3") (pintype "bidirectional"))
    )
    (net (code "59") (name "Net-(RLY4-COIL2)") (class "Default")
      (node (ref "D4") (pin "A") (pinfunction "A_A") (pintype "passive"))
      (node (ref "Q4") (pin "C") (pinfunction "C_C") (pintype "passive"))
      (node (ref "RLY4") (pin "1") (pinfunction "COIL2_1") (pintype "bidirectional"))
    )
    (net (code "60") (name "Net-(RLY4-MAIN)") (class "Default")
      (node (ref "JP5") (pin "1") (pinfunction "1_1") (pintype "passive"))
      (node (ref "RLY4") (pin "4") (pinfunction "MAIN_4") (pintype "bidirectional"))
    )
    (net (code "61") (name "Net-(RLY4-NO)") (class "Default")
      (node (ref "JP5") (pin "2") (pinfunction "2_2") (pintype "passive"))
      (node (ref "RLY4") (pin "3") (pinfunction "NO_3") (pintype "bidirectional"))
    )
    (net (code "62") (name "Net-(RLY5-COIL2)") (class "Default")
      (node (ref "D5") (pin "A") (pinfunction "A_A") (pintype "passive"))
      (node (ref "Q5") (pin "C") (pinfunction "C_C") (pintype "passive"))
      (node (ref "RLY5") (pin "1") (pinfunction "COIL2_1") (pintype "bidirectional"))
    )
    (net (code "63") (name "Net-(RLY5-MAIN)") (class "Default")
      (node (ref "JP6") (pin "1") (pinfunction "1_1") (pintype "passive"))
      (node (ref "RLY5") (pin "4") (pinfunction "MAIN_4") (pintype "bidirectional"))
    )
    (net (code "64") (name "Net-(RLY5-NO)") (class "Default")
      (node (ref "JP6") (pin "2") (pinfunction "2_2") (pintype "passive"))
      (node (ref "RLY5") (pin "3") (pinfunction "NO_3") (pintype "bidirectional"))
    )
    (net (code "65") (name "Net-(RLY6-COIL2)") (class "Default")
      (node (ref "D6") (pin "A") (pinfunction "A_A") (pintype "passive"))
      (node (ref "Q6") (pin "C") (pinfunction "C_C") (pintype "passive"))
      (node (ref "RLY6") (pin "1") (pinfunction "COIL2_1") (pintype "bidirectional"))
    )
    (net (code "66") (name "Net-(RLY6-MAIN)") (class "Default")
      (node (ref "JP7") (pin "1") (pinfunction "1_1") (pintype "passive"))
      (node (ref "RLY6") (pin "4") (pinfunction "MAIN_4") (pintype "bidirectional"))
    )
    (net (code "67") (name "Net-(RLY6-NO)") (class "Default")
      (node (ref "JP7") (pin "2") (pinfunction "2_2") (pintype "passive"))
      (node (ref "RLY6") (pin "3") (pinfunction "NO_3") (pintype "bidirectional"))
    )
    (net (code "68") (name "Net-(RLY7-COIL2)") (class "Default")
      (node (ref "D7") (pin "A") (pinfunction "A_A") (pintype "passive"))
      (node (ref "Q7") (pin "C") (pinfunction "C_C") (pintype "passive"))
      (node (ref "RLY7") (pin "1") (pinfunction "COIL2_1") (pintype "bidirectional"))
    )
    (net (code "69") (name "Net-(RLY7-MAIN)") (class "Default")
      (node (ref "JP8") (pin "1") (pinfunction "1_1") (pintype "passive"))
      (node (ref "RLY7") (pin "4") (pinfunction "MAIN_4") (pintype "bidirectional"))
    )
    (net (code "70") (name "Net-(RLY7-NO)") (class "Default")
      (node (ref "JP8") (pin "2") (pinfunction "2_2") (pintype "passive"))
      (node (ref "RLY7") (pin "3") (pinfunction "NO_3") (pintype "bidirectional"))
    )
    (net (code "71") (name "Net-(RLY8-COIL2)") (class "Default")
      (node (ref "D8") (pin "A") (pinfunction "A_A") (pintype "passive"))
      (node (ref "Q8") (pin "C") (pinfunction "C_C") (pintype "passive"))
      (node (ref "RLY8") (pin "1") (pinfunction "COIL2_1") (pintype "bidirectional"))
    )
    (net (code "72") (name "Net-(RLY8-MAIN)") (class "Default")
      (node (ref "JP9") (pin "1") (pinfunction "1_1") (pintype "passive"))
      (node (ref "RLY8") (pin "4") (pinfunction "MAIN_4") (pintype "bidirectional"))
    )
    (net (code "73") (name "Net-(RLY8-NO)") (class "Default")
      (node (ref "JP9") (pin "2") (pinfunction "2_2") (pintype "passive"))
      (node (ref "RLY8") (pin "3") (pinfunction "NO_3") (pintype "bidirectional"))
    )
    (net (code "74") (name "Net-(U1-AREF)") (class "Default")
      (node (ref "C8") (pin "2") (pinfunction "2_2") (pintype "passive"))
      (node (ref "U1") (pin "20") (pinfunction "AREF_20") (pintype "bidirectional"))
    )
    (net (code "75") (name "Net-(U1-PB6(XTAL1{slash}TOSC1))") (class "Default")
      (node (ref "C6") (pin "2") (pinfunction "2_2") (pintype "passive"))
      (node (ref "U1") (pin "7") (pinfunction "PB6(XTAL1/TOSC1)_7") (pintype "bidirectional"))
      (node (ref "Y1") (pin "2") (pinfunction "2_2") (pintype "passive"))
    )
    (net (code "76") (name "Net-(U1-PB7(XTAL2{slash}TOSC2))") (class "Default")
      (node (ref "C7") (pin "2") (pinfunction "2_2") (pintype "passive"))
      (node (ref "U1") (pin "8") (pinfunction "PB7(XTAL2/TOSC2)_8") (pintype "bidirectional"))
      (node (ref "Y1") (pin "1") (pinfunction "1_1") (pintype "passive"))
    )
    (net (code "77") (name "Net-(U1-PC2(ADC2))") (class "Default")
      (node (ref "JP14") (pin "1") (pinfunction "1_1") (pintype "passive"))
      (node (ref "U1") (pin "25") (pinfunction "PC2(ADC2)_25") (pintype "bidirectional"))
    )
    (net (code "78") (name "Net-(U1-PC3(ADC3))") (class "Default")
      (node (ref "JP14") (pin "2") (pinfunction "2_2") (pintype "passive"))
      (node (ref "U1") (pin "26") (pinfunction "PC3(ADC3)_26") (pintype "bidirectional"))
    )
    (net (code "79") (name "Net-(U18-1)") (class "Default")
      (node (ref "C11") (pin "2") (pinfunction "2_2") (pintype "passive"))
      (node (ref "D9") (pin "C") (pinfunction "C_C") (pintype "passive"))
      (node (ref "U17") (pin "SW") (pinfunction "SW_SW") (pintype "bidirectional"))
      (node (ref "U18") (pin "P$1") (pinfunction "1_P$1") (pintype "passive"))
    )
    (net (code "80") (name "RELAY1") (class "Default")
      (node (ref "R2") (pin "2") (pinfunction "2_2") (pintype "passive"))
      (node (ref "U1") (pin "1") (pinfunction "PD3(INT1)_1") (pintype "bidirectional"))
    )
    (net (code "81") (name "RELAY2") (class "Default")
      (node (ref "R4") (pin "2") (pinfunction "2_2") (pintype "passive"))
      (node (ref "U1") (pin "2") (pinfunction "PD4(XCK/T0)_2") (pintype "bidirectional"))
    )
    (net (code "82") (name "RELAY3") (class "Default")
      (node (ref "R6") (pin "2") (pinfunction "2_2") (pintype "passive"))
      (node (ref "U1") (pin "9") (pinfunction "PD5(T1)_9") (pintype "bidirectional"))
    )
    (net (code "83") (name "RELAY4") (class "Default")
      (node (ref "R8") (pin "2") (pinfunction "2_2") (pintype "passive"))
      (node (ref "U1") (pin "10") (pinfunction "PD6(AIN0)_10") (pintype "bidirectional"))
    )
    (net (code "84") (name "RELAY5") (class "Default")
      (node (ref "R16") (pin "2") (pinfunction "2_2") (pintype "passive"))
      (node (ref "U1") (pin "11") (pinfunction "PD7(AIN1)_11") (pintype "bidirectional"))
    )
    (net (code "85") (name "RELAY6") (class "Default")
      (node (ref "R10") (pin "2") (pinfunction "2_2") (pintype "passive"))
      (node (ref "U1") (pin "12") (pinfunction "PB0(ICP)_12") (pintype "bidirectional"))
    )
    (net (code "86") (name "RELAY7") (class "Default")
      (node (ref "R12") (pin "2") (pinfunction "2_2") (pintype "passive"))
      (node (ref "U1") (pin "13") (pinfunction "PB1(OC1A)_13") (pintype "bidirectional"))
    )
    (net (code "87") (name "RELAY8") (class "Default")
      (node (ref "R14") (pin "2") (pinfunction "2_2") (pintype "passive"))
      (node (ref "U1") (pin "14") (pinfunction "PB2(SS/OC1B)_14") (pintype "bidirectional"))
    )
    (net (code "88") (name "RESET") (class "Default")
      (node (ref "J1") (pin "5") (pinfunction "5_5") (pintype "passive"))
      (node (ref "R1") (pin "1") (pinfunction "1_1") (pintype "passive"))
      (node (ref "U1") (pin "29") (pinfunction "PC6(/RESET)_29") (pintype "bidirectional"))
    )
    (net (code "89") (name "ROCKLIGHTS") (class "Default")
      (node (ref "R20") (pin "2") (pinfunction "2_2") (pintype "passive"))
      (node (ref "U1") (pin "23") (pinfunction "PC0(ADC0)_23") (pintype "bidirectional"))
      (node (ref "U19") (pin "2") (pinfunction "G_2") (pintype "passive"))
    )
    (net (code "90") (name "RX") (class "Default")
      (node (ref "BLUETOOTH") (pin "4") (pinfunction "4_4") (pintype "passive"))
      (node (ref "JP15") (pin "2") (pinfunction "2_2") (pintype "passive"))
      (node (ref "U1") (pin "30") (pinfunction "PD0(RXD)_30") (pintype "bidirectional"))
    )
    (net (code "91") (name "RX-JUMP") (class "Default")
      (node (ref "JP11") (pin "1") (pinfunction "1_1") (pintype "passive"))
      (node (ref "JP15") (pin "1") (pinfunction "1_1") (pintype "passive"))
    )
    (net (code "92") (name "SCK") (class "Default")
      (node (ref "J1") (pin "3") (pinfunction "3_3") (pintype "passive"))
      (node (ref "U1") (pin "17") (pinfunction "PB5(SCK)_17") (pintype "bidirectional"))
    )
    (net (code "93") (name "SCL") (class "Default")
      (node (ref "I2C/IO") (pin "4") (pinfunction "4_4") (pintype "passive"))
      (node (ref "U1") (pin "28") (pinfunction "PC5(ADC5/SCL)_28") (pintype "bidirectional"))
    )
    (net (code "94") (name "SDA") (class "Default")
      (node (ref "I2C/IO") (pin "3") (pinfunction "3_3") (pintype "passive"))
      (node (ref "U1") (pin "27") (pinfunction "PC4(ADC4/SDA)_27") (pintype "bidirectional"))
    )
    (net (code "95") (name "TX") (class "Default")
      (node (ref "BLUETOOTH") (pin "5") (pinfunction "5_5") (pintype "passive"))
      (node (ref "JP15") (pin "4") (pinfunction "4_4") (pintype "passive"))
      (node (ref "U1") (pin "31") (pinfunction "PD1(TXD)_31") (pintype "bidirectional"))
    )
    (net (code "96") (name "TX-JUMP") (class "Default")
      (node (ref "JP11") (pin "2") (pinfunction "2_2") (pintype "passive"))
      (node (ref "JP15") (pin "3") (pinfunction "3_3") (pintype "passive"))
    )
    (net (code "97") (name "unconnected-(RLY1-NC-Pad2)") (class "Default")
      (node (ref "RLY1") (pin "2") (pinfunction "NC_2") (pintype "bidirectional"))
    )
    (net (code "98") (name "unconnected-(RLY2-NC-Pad2)") (class "Default")
      (node (ref "RLY2") (pin "2") (pinfunction "NC_2") (pintype "bidirectional"))
    )
    (net (code "99") (name "unconnected-(RLY3-NC-Pad2)") (class "Default")
      (node (ref "RLY3") (pin "2") (pinfunction "NC_2") (pintype "bidirectional"))
    )
    (net (code "100") (name "unconnected-(RLY4-NC-Pad2)") (class "Default")
      (node (ref "RLY4") (pin "2") (pinfunction "NC_2") (pintype "bidirectional"))
    )
    (net (code "101") (name "unconnected-(RLY5-NC-Pad2)") (class "Default")
      (node (ref "RLY5") (pin "2") (pinfunction "NC_2") (pintype "bidirectional"))
    )
    (net (code "102") (name "unconnected-(RLY6-NC-Pad2)") (class "Default")
      (node (ref "RLY6") (pin "2") (pinfunction "NC_2") (pintype "bidirectional"))
    )
    (net (code "103") (name "unconnected-(RLY7-NC-Pad2)") (class "Default")
      (node (ref "RLY7") (pin "2") (pinfunction "NC_2") (pintype "bidirectional"))
    )
    (net (code "104") (name "unconnected-(RLY8-NC-Pad2)") (class "Default")
      (node (ref "RLY8") (pin "2") (pinfunction "NC_2") (pintype "bidirectional"))
    )
  )
)
